# Embedded_Chip.net
KiCad netlist of a schematic drawn in Altium Designer
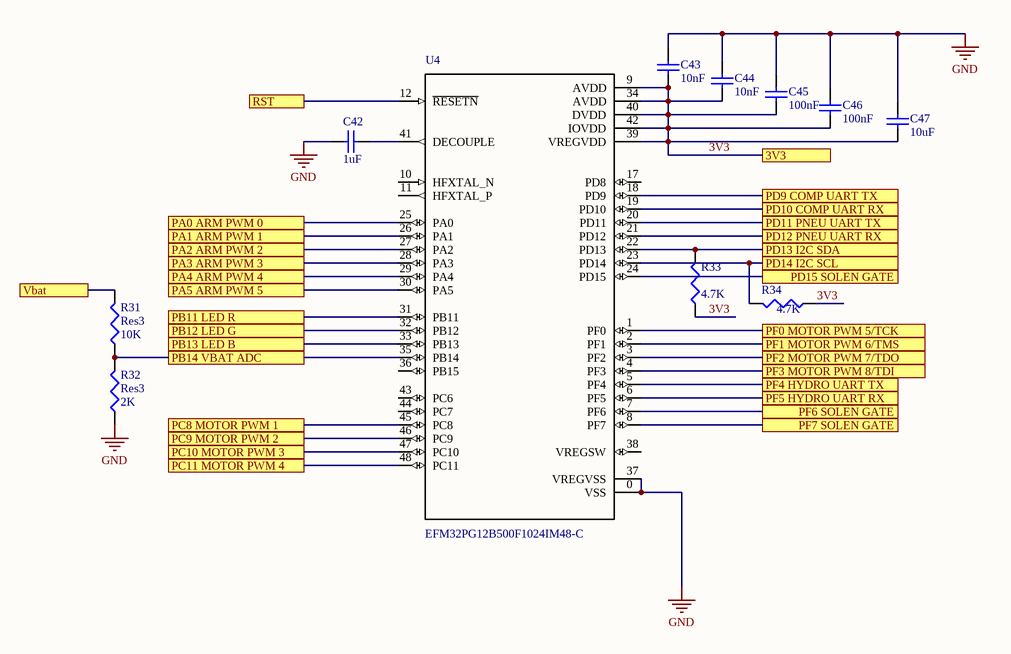
[diagram p0: Embedded_Chip.SchDoc]

(export (version "E")
  (design (tool "Eeschema 10.0.6"))
  (components
    (comp (ref "C42")
      (value "1uF")
      (footprint "C1206")
      (description "Capacitor (Semiconductor SIM Model)")
      (fields (field (name "Comment") "Cap Semi") (field (name "PUBLISHER") "Altium Limited"))
      (libsource (lib "Miscellaneous Devices") (part "Cap Semi"))
    )
    (comp (ref "C43")
      (value "10nF")
      (footprint "C1206")
      (description "Capacitor (Semiconductor SIM Model)")
      (fields (field (name "Comment") "Cap Semi") (field (name "PUBLISHER") "Altium Limited"))
      (libsource (lib "Miscellaneous Devices") (part "Cap Semi"))
    )
    (comp (ref "C44")
      (value "10nF")
      (footprint "C1206")
      (description "Capacitor (Semiconductor SIM Model)")
      (fields (field (name "Comment") "Cap Semi") (field (name "PUBLISHER") "Altium Limited"))
      (libsource (lib "Miscellaneous Devices") (part "Cap Semi"))
    )
    (comp (ref "C45")
      (value "100nF")
      (footprint "C1206")
      (description "Capacitor (Semiconductor SIM Model)")
      (fields (field (name "Comment") "Cap Semi") (field (name "PUBLISHER") "Altium Limited"))
      (libsource (lib "Miscellaneous Devices") (part "Cap Semi"))
    )
    (comp (ref "C46")
      (value "100nF")
      (footprint "C1206")
      (description "Capacitor (Semiconductor SIM Model)")
      (fields (field (name "Comment") "Cap Semi") (field (name "PUBLISHER") "Altium Limited"))
      (libsource (lib "Miscellaneous Devices") (part "Cap Semi"))
    )
    (comp (ref "C47")
      (value "10uF")
      (footprint "C1206")
      (description "Capacitor (Semiconductor SIM Model)")
      (fields (field (name "Comment") "Cap Semi") (field (name "PUBLISHER") "Altium Limited"))
      (libsource (lib "Miscellaneous Devices") (part "Cap Semi"))
    )
    (comp (ref "R31")
      (value "Res3")
      (footprint "J1-0603")
      (description "Resistor")
      (fields (field (name "ALTIUM_VALUE") "10K") (field (name "PUBLISHER") "Altium Limited"))
      (libsource (lib "Miscellaneous Devices") (part "Res3"))
    )
    (comp (ref "R32")
      (value "Res3")
      (footprint "J1-0603")
      (description "Resistor")
      (fields (field (name "ALTIUM_VALUE") "2K") (field (name "PUBLISHER") "Altium Limited"))
      (libsource (lib "Miscellaneous Devices") (part "Res3"))
    )
    (comp (ref "R33")
      (value "4.7K")
      (footprint "J1-0603")
      (description "Resistor")
      (fields (field (name "Comment") "Res3") (field (name "PUBLISHER") "Altium Limited"))
      (libsource (lib "Miscellaneous Devices") (part "Res3"))
    )
    (comp (ref "R34")
      (value "4.7K")
      (footprint "J1-0603")
      (description "Resistor")
      (fields (field (name "Comment") "Res3") (field (name "PUBLISHER") "Altium Limited"))
      (libsource (lib "Miscellaneous Devices") (part "Res3"))
    )
    (comp (ref "U4")
      (value "EFM32PG12B500F1024IM48-C")
      (footprint "QFN50P700X700X90-49N")
      (description "ARM® Cortex®-M4 Pearl Gecko Microcontroller IC 32-Bit 40MHz 1MB (1M x 8) FLASH 48-QFN (7x7)")
      (fields (field (name "MP") "EFM32PG12B500F1024GM48-B") (field (name "MF") "Silicon Labs"))
      (libsource (lib "Power_Embedded_Board_Library") (part "EFM32PG12B500F1024IM48-C"))
    )
  )
  (nets
    (net (code "1") (name "/3V3") (class "Default")
      (node (ref "C43") (pin "2") (pinfunction "2_2") (pintype "passive"))
      (node (ref "C44") (pin "2") (pinfunction "2_2") (pintype "passive"))
      (node (ref "C45") (pin "2") (pinfunction "2_2") (pintype "passive"))
      (node (ref "C46") (pin "2") (pinfunction "2_2") (pintype "passive"))
      (node (ref "C47") (pin "2") (pinfunction "2_2") (pintype "passive"))
      (node (ref "R33") (pin "1") (pinfunction "1_1") (pintype "passive"))
      (node (ref "R34") (pin "1") (pinfunction "1_1") (pintype "passive"))
      (node (ref "U4") (pin "34") (pinfunction "AVDD_34") (pintype "power_in"))
      (node (ref "U4") (pin "39") (pinfunction "VREGVDD_39") (pintype "power_in"))
      (node (ref "U4") (pin "40") (pinfunction "DVDD_40") (pintype "power_in"))
      (node (ref "U4") (pin "42") (pinfunction "IOVDD_42") (pintype "power_in"))
      (node (ref "U4") (pin "9") (pinfunction "AVDD_9") (pintype "power_in"))
    )
    (net (code "2") (name "/PA0 ARM PWM 0") (class "Default")
      (node (ref "U4") (pin "25") (pinfunction "PA0_25") (pintype "bidirectional"))
    )
    (net (code "3") (name "/PA1 ARM PWM 1") (class "Default")
      (node (ref "U4") (pin "26") (pinfunction "PA1_26") (pintype "bidirectional"))
    )
    (net (code "4") (name "/PA2 ARM PWM 2") (class "Default")
      (node (ref "U4") (pin "27") (pinfunction "PA2_27") (pintype "bidirectional"))
    )
    (net (code "5") (name "/PA3 ARM PWM 3") (class "Default")
      (node (ref "U4") (pin "28") (pinfunction "PA3_28") (pintype "bidirectional"))
    )
    (net (code "6") (name "/PA4 ARM PWM 4") (class "Default")
      (node (ref "U4") (pin "29") (pinfunction "PA4_29") (pintype "bidirectional"))
    )
    (net (code "7") (name "/PA5 ARM PWM 5") (class "Default")
      (node (ref "U4") (pin "30") (pinfunction "PA5_30") (pintype "bidirectional"))
    )
    (net (code "8") (name "/PB11 LED R") (class "Default")
      (node (ref "U4") (pin "31") (pinfunction "PB11_31") (pintype "bidirectional"))
    )
    (net (code "9") (name "/PB12 LED G") (class "Default")
      (node (ref "U4") (pin "32") (pinfunction "PB12_32") (pintype "bidirectional"))
    )
    (net (code "10") (name "/PB13 LED B") (class "Default")
      (node (ref "U4") (pin "33") (pinfunction "PB13_33") (pintype "bidirectional"))
    )
    (net (code "11") (name "/PB14 VBAT ADC") (class "Default")
      (node (ref "R31") (pin "1") (pinfunction "1_1") (pintype "passive"))
      (node (ref "R32") (pin "2") (pinfunction "2_2") (pintype "passive"))
      (node (ref "U4") (pin "35") (pinfunction "PB14_35") (pintype "bidirectional"))
    )
    (net (code "12") (name "/PC8 MOTOR PWM 1") (class "Default")
      (node (ref "U4") (pin "45") (pinfunction "PC8_45") (pintype "bidirectional"))
    )
    (net (code "13") (name "/PC9 MOTOR PWM 2") (class "Default")
      (node (ref "U4") (pin "46") (pinfunction "PC9_46") (pintype "bidirectional"))
    )
    (net (code "14") (name "/PC10 MOTOR PWM 3") (class "Default")
      (node (ref "U4") (pin "47") (pinfunction "PC10_47") (pintype "bidirectional"))
    )
    (net (code "15") (name "/PC11 MOTOR PWM 4") (class "Default")
      (node (ref "U4") (pin "48") (pinfunction "PC11_48") (pintype "bidirectional"))
    )
    (net (code "16") (name "/PD9 COMP UART TX") (class "Default")
      (node (ref "U4") (pin "18") (pinfunction "PD9_18") (pintype "bidirectional"))
    )
    (net (code "17") (name "/PD10 COMP UART RX") (class "Default")
      (node (ref "U4") (pin "19") (pinfunction "PD10_19") (pintype "bidirectional"))
    )
    (net (code "18") (name "/PD11 PNEU UART TX") (class "Default")
      (node (ref "U4") (pin "20") (pinfunction "PD11_20") (pintype "bidirectional"))
    )
    (net (code "19") (name "/PD12 PNEU UART RX") (class "Default")
      (node (ref "U4") (pin "21") (pinfunction "PD12_21") (pintype "bidirectional"))
    )
    (net (code "20") (name "/PD13 I2C SDA") (class "Default")
      (node (ref "R33") (pin "2") (pinfunction "2_2") (pintype "passive"))
      (node (ref "U4") (pin "22") (pinfunction "PD13_22") (pintype "bidirectional"))
    )
    (net (code "21") (name "/PD14 I2C SCL") (class "Default")
      (node (ref "R34") (pin "2") (pinfunction "2_2") (pintype "passive"))
      (node (ref "U4") (pin "23") (pinfunction "PD14_23") (pintype "bidirectional"))
    )
    (net (code "22") (name "/PD15 SOLEN GATE") (class "Default")
      (node (ref "U4") (pin "24") (pinfunction "PD15_24") (pintype "bidirectional"))
    )
    (net (code "23") (name "/PF0 MOTOR PWM 5{slash}TCK") (class "Default")
      (node (ref "U4") (pin "1") (pinfunction "PF0_1") (pintype "bidirectional"))
    )
    (net (code "24") (name "/PF1 MOTOR PWM 6{slash}TMS") (class "Default")
      (node (ref "U4") (pin "2") (pinfunction "PF1_2") (pintype "bidirectional"))
    )
    (net (code "25") (name "/PF2 MOTOR PWM 7{slash}TDO") (class "Default")
      (node (ref "U4") (pin "3") (pinfunction "PF2_3") (pintype "bidirectional"))
    )
    (net (code "26") (name "/PF3 MOTOR PWM 8{slash}TDI") (class "Default")
      (node (ref "U4") (pin "4") (pinfunction "PF3_4") (pintype "bidirectional"))
    )
    (net (code "27") (name "/PF4 HYDRO UART TX") (class "Default")
      (node (ref "U4") (pin "5") (pinfunction "PF4_5") (pintype "bidirectional"))
    )
    (net (code "28") (name "/PF5 HYDRO UART RX") (class "Default")
      (node (ref "U4") (pin "6") (pinfunction "PF5_6") (pintype "bidirectional"))
    )
    (net (code "29") (name "/PF6 SOLEN GATE") (class "Default")
      (node (ref "U4") (pin "7") (pinfunction "PF6_7") (pintype "bidirectional"))
    )
    (net (code "30") (name "/PF7 SOLEN GATE") (class "Default")
      (node (ref "U4") (pin "8") (pinfunction "PF7_8") (pintype "bidirectional"))
    )
    (net (code "31") (name "/RST") (class "Default")
      (node (ref "U4") (pin "12") (pinfunction "~{RESETN}_12") (pintype "input"))
    )
    (net (code "32") (name "/Vbat") (class "Default")
      (node (ref "R31") (pin "2") (pinfunction "2_2") (pintype "passive"))
    )
    (net (code "33") (name "GND") (class "Default")
      (node (ref "C42") (pin "2") (pinfunction "2_2") (pintype "passive"))
      (node (ref "C43") (pin "1") (pinfunction "1_1") (pintype "passive"))
      (node (ref "C44") (pin "1") (pinfunction "1_1") (pintype "passive"))
      (node (ref "C45") (pin "1") (pinfunction "1_1") (pintype "passive"))
      (node (ref "C46") (pin "1") (pinfunction "1_1") (pintype "passive"))
      (node (ref "C47") (pin "1") (pinfunction "1_1") (pintype "passive"))
      (node (ref "R32") (pin "1") (pinfunction "1_1") (pintype "passive"))
      (node (ref "U4") (pin "0") (pinfunction "VSS_0") (pintype "power_in"))
      (node (ref "U4") (pin "37") (pinfunction "VREGVSS_37") (pintype "power_in"))
    )
    (net (code "34") (name "Net-(U4-DECOUPLE)") (class "Default")
      (node (ref "C42") (pin "1") (pinfunction "1_1") (pintype "passive"))
      (node (ref "U4") (pin "41") (pinfunction "DECOUPLE_41") (pintype "output"))
    )
    (net (code "35") (name "unconnected-(U4-HFXTAL_N-Pad10)") (class "Default")
      (node (ref "U4") (pin "10") (pinfunction "HFXTAL_N_10") (pintype "input"))
    )
    (net (code "36") (name "unconnected-(U4-HFXTAL_P-Pad11)") (class "Default")
      (node (ref "U4") (pin "11") (pinfunction "HFXTAL_P_11") (pintype "output"))
    )
    (net (code "37") (name "unconnected-(U4-PB15-Pad36)") (class "Default")
      (node (ref "U4") (pin "36") (pinfunction "PB15_36") (pintype "bidirectional"))
    )
    (net (code "38") (name "unconnected-(U4-PC6-Pad43)") (class "Default")
      (node (ref "U4") (pin "43") (pinfunction "PC6_43") (pintype "bidirectional"))
    )
    (net (code "39") (name "unconnected-(U4-PC7-Pad44)") (class "Default")
      (node (ref "U4") (pin "44") (pinfunction "PC7_44") (pintype "bidirectional"))
    )
    (net (code "40") (name "unconnected-(U4-PD8-Pad17)") (class "Default")
      (node (ref "U4") (pin "17") (pinfunction "PD8_17") (pintype "bidirectional"))
    )
    (net (code "41") (name "unconnected-(U4-VREGSW-Pad38)") (class "Default")
      (node (ref "U4") (pin "38") (pinfunction "VREGSW_38") (pintype "bidirectional"))
    )
  )
)
